# POTENCIA.net
KiCad netlist of a schematic drawn in Altium Designer
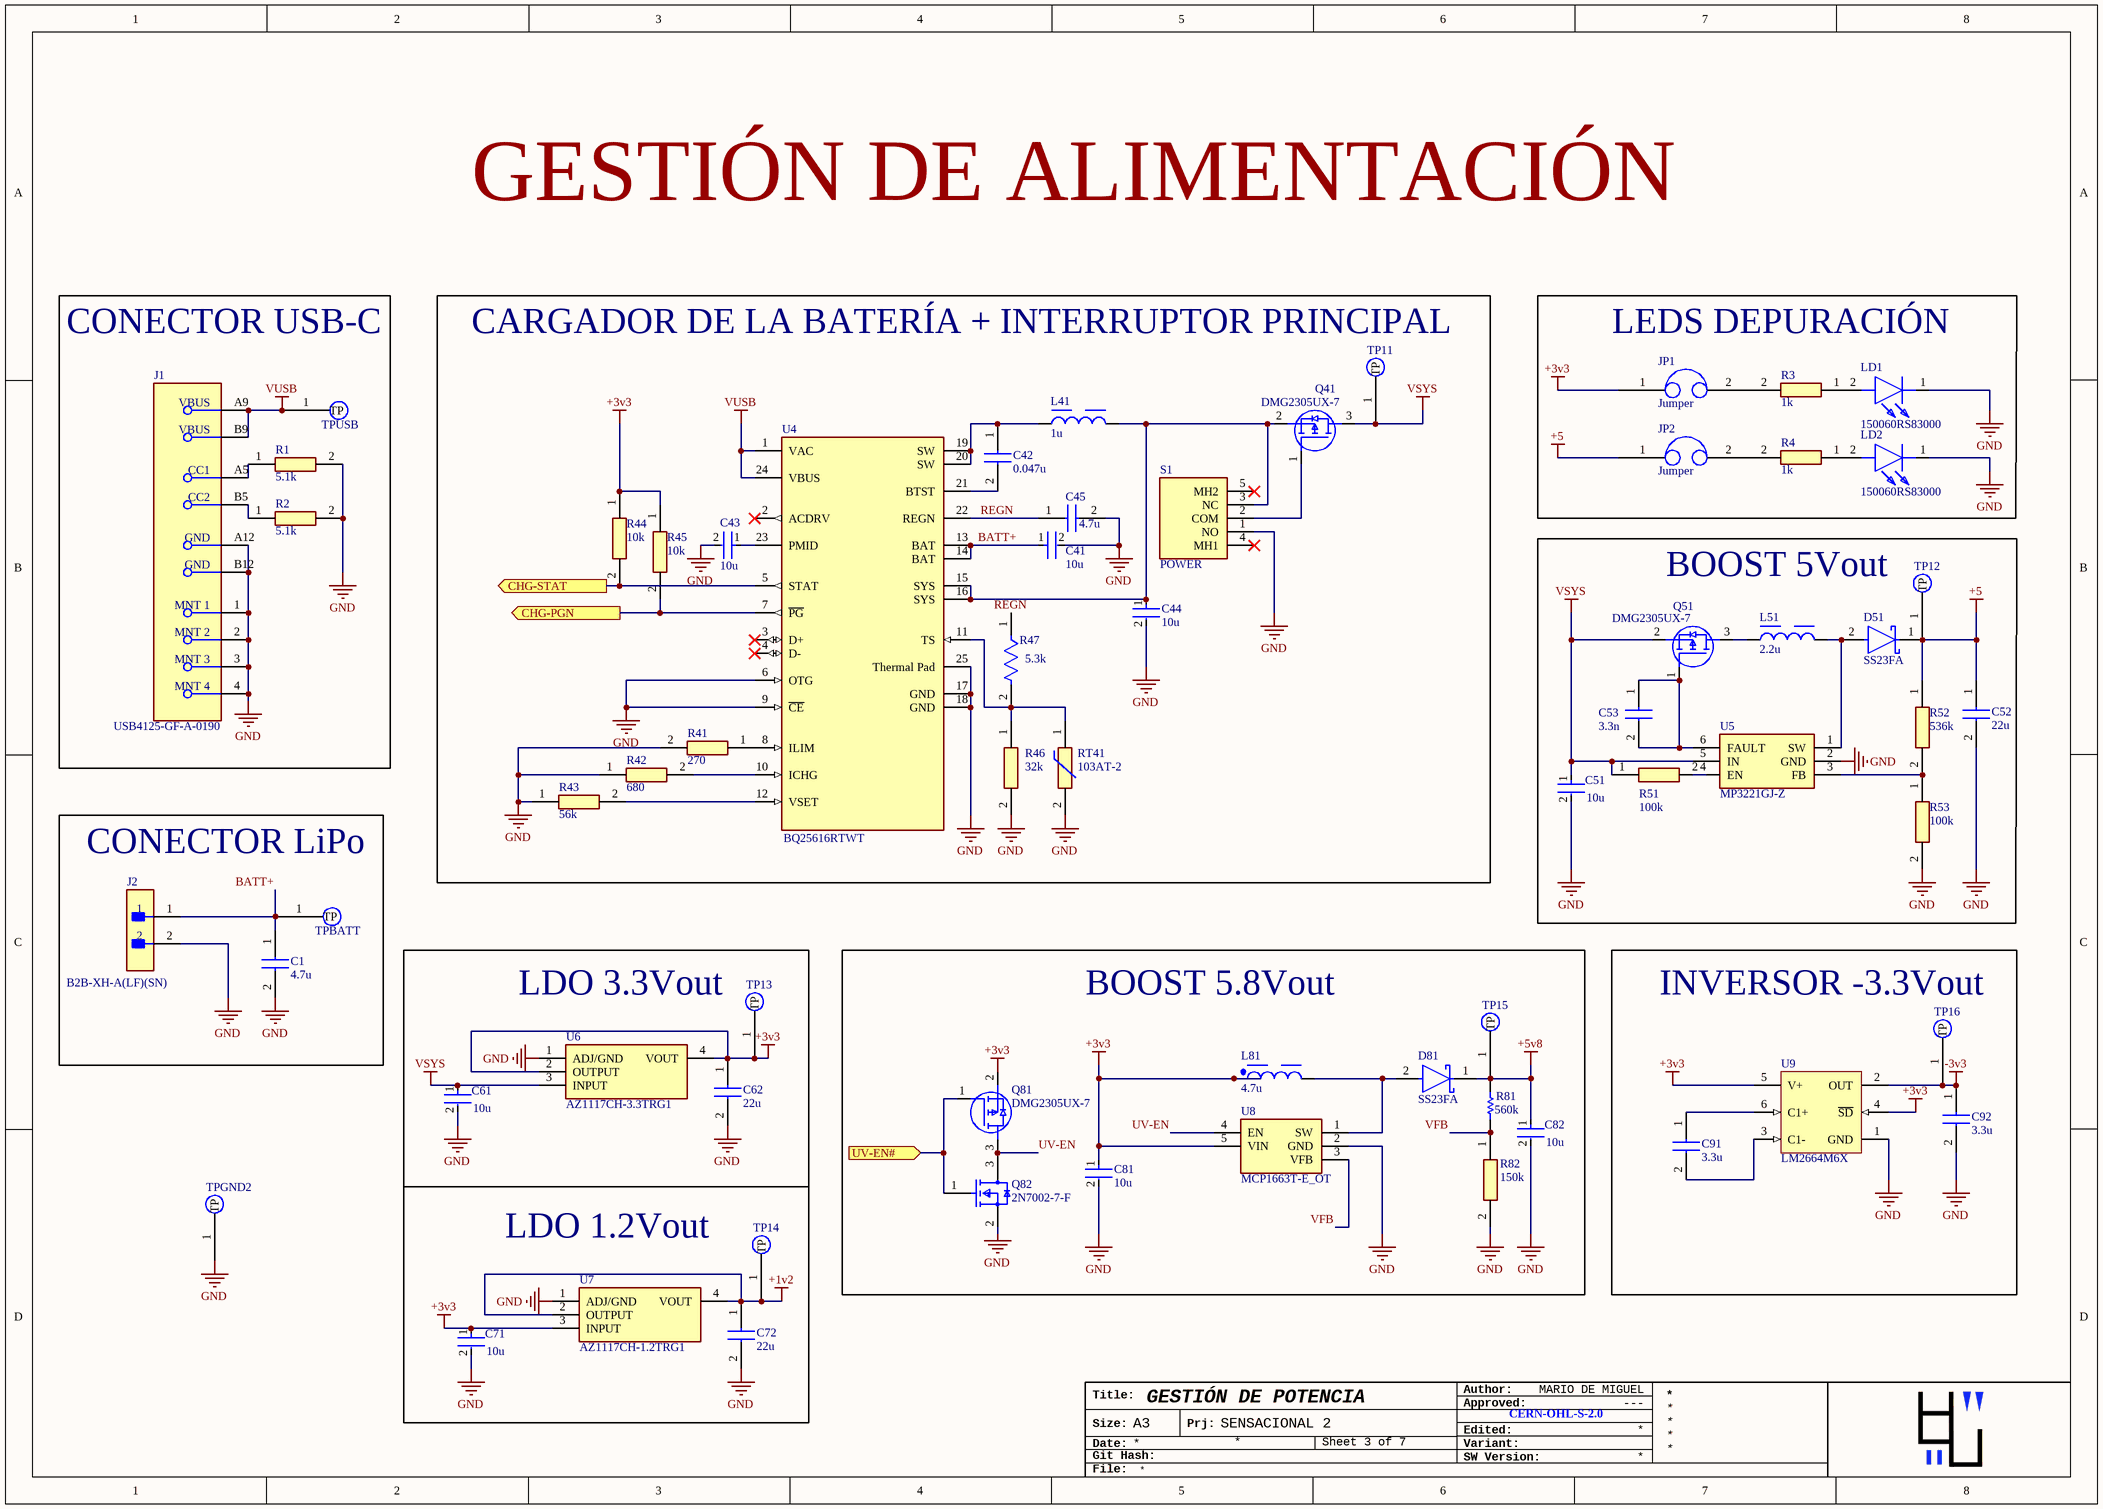
[diagram p0: POTENCIA.SchDoc]

(export (version "E")
  (design (tool "Eeschema 10.0.6"))
  (components
    (comp (ref "C1")
      (value "4.7u")
      (footprint "SamacSys:C0805")
      (description "Capacitor")
      (fields
        (field (name "MANUFACTURER_PART_NUMBER") "C0805X475J8RACAUTO")
        (field (name "MOUSER PART NUMBER") "80-C0805X475J8RAUTO")
      )
      (libsource (lib "*") (part "C0805X475J8RACAUTO"))
    )
    (comp (ref "C41")
      (value "10u")
      (footprint "FP-C2012-125-0_2-MFG")
      (description "Multilayer Ceramic Capacitors 10μF ±10% 10V X7R SMD 0805")
      (fields (field (name "TOLERANCE") "10%") (field (name "VOLTAGE") "10V"))
      (libsource (lib "Altium Content Vault") (part "b4654b650e69147ec39a6b967a45e02"))
    )
    (comp (ref "C42")
      (value "0.047u")
      (footprint "SamacSys:CAPC1608X89N")
      (description "Capacitor")
      (fields
        (field (name "MANUFACTURER_PART_NUMBER") "KAM15AR71H473KM")
        (field (name "MOUSER PART NUMBER") "581-KAM15AR71H473KM")
      )
      (libsource (lib "*") (part "KAM15AR71H473KM"))
    )
    (comp (ref "C43")
      (value "10u")
      (footprint "FP-C2012-125-0_2-MFG")
      (description "Multilayer Ceramic Capacitors 10μF ±10% 10V X7R SMD 0805")
      (fields (field (name "TOLERANCE") "10%") (field (name "VOLTAGE") "10V"))
      (libsource (lib "Altium Content Vault") (part "b4654b650e69147ec39a6b967a45e02"))
    )
    (comp (ref "C44")
      (value "10u")
      (footprint "FP-C2012-125-0_2-MFG")
      (description "Multilayer Ceramic Capacitors 10μF ±10% 10V X7R SMD 0805")
      (fields (field (name "TOLERANCE") "10%") (field (name "VOLTAGE") "10V"))
      (libsource (lib "Altium Content Vault") (part "b4654b650e69147ec39a6b967a45e02"))
    )
    (comp (ref "C45")
      (value "4.7u")
      (footprint "SamacSys:C0805")
      (description "Capacitor")
      (fields
        (field (name "MANUFACTURER_PART_NUMBER") "C0805X475J8RACAUTO")
        (field (name "MOUSER PART NUMBER") "80-C0805X475J8RAUTO")
      )
      (libsource (lib "*") (part "C0805X475J8RACAUTO"))
    )
    (comp (ref "C51")
      (value "10u")
      (footprint "FP-C2012-125-0_2-MFG")
      (description "Multilayer Ceramic Capacitors 10μF ±10% 10V X7R SMD 0805")
      (fields (field (name "TOLERANCE") "10%") (field (name "VOLTAGE") "10V"))
      (libsource (lib "Altium Content Vault") (part "b4654b650e69147ec39a6b967a45e02"))
    )
    (comp (ref "C52")
      (value "22u")
      (footprint "SamacSys:CAPC3216X200N")
      (description "Capacitor")
      (fields (field (name "MANUFACTURER_PART_NUMBER") "GCJ31CC71C226ME02L"))
      (libsource (lib "*") (part "GCJ31CC71C226ME02L"))
    )
    (comp (ref "C53")
      (value "3.3n")
      (footprint "SamacSys:CAPC2012X130N")
      (description "Capacitor")
      (fields (field (name "MANUFACTURER_PART_NUMBER") "GRM21AR7LU332KW01D"))
      (libsource (lib "*") (part "GRM21AR7LU332KW01D"))
    )
    (comp (ref "C61")
      (value "10u")
      (footprint "FP-C2012-125-0_2-MFG")
      (description "Multilayer Ceramic Capacitors 10μF ±10% 10V X7R SMD 0805")
      (fields (field (name "TOLERANCE") "10%") (field (name "VOLTAGE") "10V"))
      (libsource (lib "Altium Content Vault") (part "b4654b650e69147ec39a6b967a45e02"))
    )
    (comp (ref "C62")
      (value "22u")
      (footprint "SamacSys:CAPC3216X200N")
      (description "Capacitor")
      (fields (field (name "MANUFACTURER_PART_NUMBER") "GCJ31CC71C226ME02L"))
      (libsource (lib "*") (part "GCJ31CC71C226ME02L"))
    )
    (comp (ref "C71")
      (value "10u")
      (footprint "FP-C2012-125-0_2-MFG")
      (description "Multilayer Ceramic Capacitors 10μF ±10% 10V X7R SMD 0805")
      (fields (field (name "TOLERANCE") "10%") (field (name "VOLTAGE") "10V"))
      (libsource (lib "Altium Content Vault") (part "b4654b650e69147ec39a6b967a45e02"))
    )
    (comp (ref "C72")
      (value "22u")
      (footprint "SamacSys:CAPC3216X200N")
      (description "Capacitor")
      (fields (field (name "MANUFACTURER_PART_NUMBER") "GCJ31CC71C226ME02L"))
      (libsource (lib "*") (part "GCJ31CC71C226ME02L"))
    )
    (comp (ref "C81")
      (value "10u")
      (footprint "FP-C2012-125-0_2-MFG")
      (description "Multilayer Ceramic Capacitors 10μF ±10% 10V X7R SMD 0805")
      (fields (field (name "TOLERANCE") "10%") (field (name "VOLTAGE") "10V"))
      (libsource (lib "Altium Content Vault") (part "b4654b650e69147ec39a6b967a45e02"))
    )
    (comp (ref "C82")
      (value "10u")
      (footprint "FP-C2012-125-0_2-MFG")
      (description "Multilayer Ceramic Capacitors 10μF ±10% 10V X7R SMD 0805")
      (fields (field (name "TOLERANCE") "10%") (field (name "VOLTAGE") "10V"))
      (libsource (lib "Altium Content Vault") (part "b4654b650e69147ec39a6b967a45e02"))
    )
    (comp (ref "C91")
      (value "3.3u")
      (footprint "SamacSys:CAPC1608X80N")
      (description "Capacitor")
      (fields
        (field (name "MANUFACTURER_PART_NUMBER") "C1608X5R1V335K080AC")
        (field (name "MOUSER PART NUMBER") "810-C1608X5R1V335KAC")
      )
      (libsource (lib "*") (part "C1608X5R1V335K080AC"))
    )
    (comp (ref "C92")
      (value "3.3u")
      (footprint "SamacSys:CAPC1608X80N")
      (description "Capacitor")
      (fields
        (field (name "MANUFACTURER_PART_NUMBER") "C1608X5R1V335K080AC")
        (field (name "MOUSER PART NUMBER") "810-C1608X5R1V335KAC")
      )
      (libsource (lib "*") (part "C1608X5R1V335K080AC"))
    )
    (comp (ref "D51")
      (value "SS23FA")
      (footprint "FP-425AB-MFG")
      (description "SS23FA 2 A, 30 V Surface Mount Schottky Barrier Rectifiers")
      (libsource (lib "Altium Content Vault") (part "1d6ec82d83fb6aee721767c19dac4b9"))
    )
    (comp (ref "D81")
      (value "SS23FA")
      (footprint "FP-425AB-MFG")
      (description "SS23FA 2 A, 30 V Surface Mount Schottky Barrier Rectifiers")
      (libsource (lib "Altium Content Vault") (part "1d6ec82d83fb6aee721767c19dac4b9"))
    )
    (comp (ref "J1")
      (value "USB4125-GF-A-0190")
      (footprint "FP-USB4125-GF-A-0190-MFG")
      (description "CONN RCPT TYPE C 6P SMD RA")
      (libsource (lib "Altium Content Vault") (part "a055484d46e58b234844902c9fd883a"))
    )
    (comp (ref "J2")
      (value "B2B-XH-A(LF)(SN)")
      (footprint "FP-B2B-XH-A_LF_SN-MFG")
      (description "CONN HEADER VERT 2POS 2.5MM")
      (libsource (lib "Altium Content Vault") (part "3bc925449376181038e59eaffc5286c"))
    )
    (comp (ref "JP1") (value "Jumper") (footprint "JUMPER_SHUNT") (libsource (lib "headers") (part "Shunt")))
    (comp (ref "JP2") (value "Jumper") (footprint "JUMPER_SHUNT") (libsource (lib "headers") (part "Shunt")))
    (comp (ref "L41")
      (value "1u")
      (footprint "WE-MAPI_3015")
      (fields (field (name "TOLERANCE") "20%"))
      (libsource (lib "Altium Content Vault") (part "Inductor - 3"))
    )
    (comp (ref "L51")
      (value "2.2u")
      (footprint "WE-LHMI_4012")
      (description "74437321022 General Purpose Inductor, 2.2uH, 20%, 1 Element, Powdered Iron-Core, SMD, 1816")
      (fields (field (name "TOLERANCE") "20%"))
      (libsource (lib "Altium Content Vault") (part "Inductor - 3"))
    )
    (comp (ref "L81")
      (value "4.7u")
      (footprint "WE-PD_7332")
      (fields (field (name "TOLERANCE") "20%"))
      (libsource (lib "Altium Content Vault") (part "Inductor - 2"))
    )
    (comp (ref "LD1")
      (value "150060RS83000")
      (footprint "SamacSys:LEDC1608X95N")
      (description "LED")
      (libsource (lib "*") (part "150060RS83000"))
    )
    (comp (ref "LD2")
      (value "150060RS83000")
      (footprint "SamacSys:LEDC1608X95N")
      (description "LED")
      (libsource (lib "*") (part "150060RS83000"))
    )
    (comp (ref "Q41")
      (value "DMG2305UX-7")
      (footprint "SamacSys:SOT96P240X115-3N")
      (description "MOSFET (P-Channel)")
      (fields (field (name "MOUSER PART NUMBER") "621-DMG2305UX-7"))
      (libsource (lib "*") (part "DMG2305UX-7"))
    )
    (comp (ref "Q51")
      (value "DMG2305UX-7")
      (footprint "SamacSys:SOT96P240X115-3N")
      (description "MOSFET (P-Channel)")
      (fields (field (name "MOUSER PART NUMBER") "621-DMG2305UX-7"))
      (libsource (lib "*") (part "DMG2305UX-7"))
    )
    (comp (ref "Q81")
      (value "DMG2305UX-7")
      (footprint "SamacSys:SOT96P240X115-3N")
      (description "MOSFET (P-Channel)")
      (fields (field (name "MOUSER PART NUMBER") "621-DMG2305UX-7"))
      (libsource (lib "*") (part "DMG2305UX-7"))
    )
    (comp (ref "Q82")
      (value "2N7002-7-F")
      (footprint "FP-SOT23-MFG")
      (description "MOSFET N-CH 60V 115MA SOT23-3")
      (fields (field (name "VOLTAGE") "60V"))
      (libsource (lib "Altium Content Vault") (part "3b9c635fedb024a5347a57b145af9cc"))
    )
    (comp (ref "R1")
      (value "5.1k")
      (footprint "SamacSys:RESC1608X55N")
      (description "Resistor")
      (fields
        (field (name "MANUFACTURER_PART_NUMBER") "RC0603FR-075K1L")
        (field (name "MOUSER PART NUMBER") "603-RC0603FR-075K1L")
      )
      (libsource (lib "*") (part "RC0603FR-075K1L"))
    )
    (comp (ref "R2")
      (value "5.1k")
      (footprint "SamacSys:RESC1608X55N")
      (description "Resistor")
      (fields
        (field (name "MANUFACTURER_PART_NUMBER") "RC0603FR-075K1L")
        (field (name "MOUSER PART NUMBER") "603-RC0603FR-075K1L")
      )
      (libsource (lib "*") (part "RC0603FR-075K1L"))
    )
    (comp (ref "R3")
      (value "1k")
      (footprint "SamacSys:ERA6AEB101V")
      (description "Resistor")
      (fields
        (field (name "MANUFACTURER_PART_NUMBER") "ERA-6ARW102V")
        (field (name "MOUSER PART NUMBER") "667-ERA-6ARW102V")
      )
      (libsource (lib "*") (part "ERA-6ARW102V"))
    )
    (comp (ref "R4")
      (value "1k")
      (footprint "SamacSys:ERA6AEB101V")
      (description "Resistor")
      (fields
        (field (name "MANUFACTURER_PART_NUMBER") "ERA-6ARW102V")
        (field (name "MOUSER PART NUMBER") "667-ERA-6ARW102V")
      )
      (libsource (lib "*") (part "ERA-6ARW102V"))
    )
    (comp (ref "R41")
      (value "270")
      (footprint "SamacSys:ERA3AEB101V")
      (description "Resistor")
      (fields
        (field (name "MANUFACTURER_PART_NUMBER") "ERA-3AEB271V")
        (field (name "MOUSER PART NUMBER") "667-ERA-3AEB271V")
      )
      (libsource (lib "*") (part "ERA-3AEB271V"))
    )
    (comp (ref "R42")
      (value "680")
      (footprint "SamacSys:RESC1608X55N")
      (description "Resistor")
      (fields
        (field (name "MANUFACTURER_PART_NUMBER") "CR0603-FX-6800ELF")
        (field (name "MOUSER PART NUMBER") "652-CR0603FX-6800ELF")
      )
      (libsource (lib "*") (part "CR0603-FX-6800ELF"))
    )
    (comp (ref "R43")
      (value "56k")
      (footprint "SamacSys:ERA3AEB101V")
      (description "Resistor")
      (fields
        (field (name "MANUFACTURER_PART_NUMBER") "ERA-3ARB563V")
        (field (name "MOUSER PART NUMBER") "667-ERA-3ARB563V")
      )
      (libsource (lib "*") (part "ERA-3ARB563V"))
    )
    (comp (ref "R44")
      (value "10k")
      (footprint "SamacSys:RESC1005X40N")
      (description "Resistor")
      (fields
        (field (name "MANUFACTURER_PART_NUMBER") "RCA040210K0JNED")
        (field (name "MOUSER PART NUMBER") "71-RCA040210K0JNED")
      )
      (libsource (lib "*") (part "RCA040210K0JNED"))
    )
    (comp (ref "R45")
      (value "10k")
      (footprint "SamacSys:RESC1005X40N")
      (description "Resistor")
      (fields
        (field (name "MANUFACTURER_PART_NUMBER") "RCA040210K0JNED")
        (field (name "MOUSER PART NUMBER") "71-RCA040210K0JNED")
      )
      (libsource (lib "*") (part "RCA040210K0JNED"))
    )
    (comp (ref "R46")
      (value "32k")
      (footprint "SamacSys:RESC1608X55N")
      (description "Resistor")
      (fields
        (field (name "MANUFACTURER_PART_NUMBER") "RT0603BRD0732KL")
        (field (name "MOUSER PART NUMBER") "603-RT0603BRD0732KL")
      )
      (libsource (lib "*") (part "RT0603BRD0732KL"))
    )
    (comp (ref "R47")
      (value "5.3k")
      (footprint "FP-TNPW0603-e3-MFG")
      (description "RES 5.3K OHM 0.1% 1/10W 0603")
      (fields (field (name "TOLERANCE") "0.1%"))
      (libsource (lib "Altium Content Vault") (part "1029c3af85768c4190bb7ad29bc67b5"))
    )
    (comp (ref "R51")
      (value "100k")
      (footprint "SamacSys:ERA3AEB101V")
      (description "Resistor")
      (fields
        (field (name "MANUFACTURER_PART_NUMBER") "ERA-3AED104V")
        (field (name "MOUSER PART NUMBER") "667-ERA-3AED104V")
      )
      (libsource (lib "*") (part "ERA-3AED104V"))
    )
    (comp (ref "R52")
      (value "536k")
      (footprint "SamacSys:RESC1608X55N")
      (description "Resistor")
      (fields
        (field (name "MANUFACTURER_PART_NUMBER") "ERJ-3EKF5363V")
        (field (name "MOUSER PART NUMBER") "667-ERJ-3EKF5363V")
      )
      (libsource (lib "*") (part "ERJ-3EKF5363V"))
    )
    (comp (ref "R53")
      (value "100k")
      (footprint "SamacSys:ERA3AEB101V")
      (description "Resistor")
      (fields
        (field (name "MANUFACTURER_PART_NUMBER") "ERA-3AED104V")
        (field (name "MOUSER PART NUMBER") "667-ERA-3AED104V")
      )
      (libsource (lib "") (part "ERA-3AED104V_1"))
    )
    (comp (ref "R81")
      (value "560k")
      (footprint "RESC1608X55X30ML15T15")
      (fields (field (name "MANUFACTURER") "Panasonic") (field (name "PART NUMBER") "ERJ-3GEYJ564V"))
      (libsource (lib "Altium Content Vault") (part "RES"))
    )
    (comp (ref "R82")
      (value "150k")
      (footprint "SamacSys:RESC1608X55N")
      (description "Resistor")
      (fields
        (field (name "MANUFACTURER_PART_NUMBER") "ERJ-S03J154V")
        (field (name "MOUSER PART NUMBER") "667-ERJ-S03J154V")
      )
      (libsource (lib "*") (part "ERJ-S03J154V"))
    )
    (comp (ref "RT41")
      (value "103AT-2")
      (footprint "SamacSys:103AT2")
      (description "Thermistor")
      (fields (field (name "MOUSER PART NUMBER") "954-103AT-2"))
      (libsource (lib "*") (part "103AT-2"))
    )
    (comp (ref "S1")
      (value "POWER")
      (footprint "SamacSys:OS102011MS2QS1")
      (description "Switch")
      (fields
        (field (name "MANUFACTURER_PART_NUMBER") "OS102011MS2QS1")
        (field (name "MOUSER PART NUMBER") "611-OS102011MS2QS1")
      )
      (libsource (lib "*") (part "OS102011MS2QS1"))
    )
    (comp (ref "TP11")
      (value "Testpoint")
      (footprint "Testpoint_TH")
      (libsource (lib "headers") (part "Testpoint"))
    )
    (comp (ref "TP12")
      (value "Testpoint")
      (footprint "Testpoint_TH")
      (libsource (lib "headers") (part "Testpoint"))
    )
    (comp (ref "TP13")
      (value "Testpoint")
      (footprint "Testpoint_TH")
      (libsource (lib "headers") (part "Testpoint"))
    )
    (comp (ref "TP14")
      (value "Testpoint")
      (footprint "Testpoint_TH")
      (libsource (lib "headers") (part "Testpoint"))
    )
    (comp (ref "TP15")
      (value "Testpoint")
      (footprint "Testpoint_TH")
      (libsource (lib "headers") (part "Testpoint"))
    )
    (comp (ref "TP16")
      (value "Testpoint")
      (footprint "Testpoint_TH")
      (libsource (lib "headers") (part "Testpoint"))
    )
    (comp (ref "TPBATT")
      (value "Testpoint")
      (footprint "Testpoint_TH")
      (libsource (lib "headers") (part "Testpoint"))
    )
    (comp (ref "TPGND2")
      (value "Testpoint")
      (footprint "Testpoint_TH")
      (libsource (lib "headers") (part "Testpoint"))
    )
    (comp (ref "TPUSB")
      (value "Testpoint")
      (footprint "Testpoint_TH")
      (libsource (lib "headers") (part "Testpoint"))
    )
    (comp (ref "U4")
      (value "BQ25616RTWT")
      (footprint "FP-RTW0024H-IPC_B")
      (description "BQ25616RTWR/T")
      (libsource (lib "Altium Content Vault") (part "cab04b428aadb88d2d607b4ef955cae"))
    )
    (comp (ref "U5")
      (value "MP3221GJ-Z")
      (footprint "SamacSys:SOT95P280X100-6N")
      (description "Integrated Circuit")
      (fields (field (name "MOUSER PART NUMBER") "946-MP3221GJ-Z"))
      (libsource (lib "*") (part "MP3221GJ-Z"))
    )
    (comp (ref "U6")
      (value "AZ1117CH-3.3TRG1")
      (footprint "SamacSys:SOT230P700X180-4N")
      (description "Integrated Circuit")
      (fields (field (name "MOUSER PART NUMBER") "621-AZ1117CH-3.3TRG1"))
      (libsource (lib "SamacSys") (part "AZ1117CH-3.3TRG1"))
    )
    (comp (ref "U7")
      (value "AZ1117CH-1.2TRG1")
      (footprint "SamacSys:SOT230P700X180-4N")
      (description "Integrated Circuit")
      (fields (field (name "MOUSER PART NUMBER") "621-AZ1117CH-1.2TRG1"))
      (libsource (lib "SamacSys") (part "AZ1117CH-1.2TRG1"))
    )
    (comp (ref "U8")
      (value "MCP1663T-E_OT")
      (footprint "SamacSys:SOT95P270X145-5N")
      (description "Integrated Circuit")
      (fields
        (field (name "MANUFACTURER_PART_NUMBER") "MCP1663T-E/OT")
        (field (name "MOUSER PART NUMBER") "579-MCP1663T-E/OT")
      )
      (libsource (lib "*") (part "MCP1663T-E_OT"))
    )
    (comp (ref "U9")
      (value "LM2664M6X")
      (footprint "DBV0006A_N")
      (description "Switched Capacitor Voltage Converter, 6-pin SOT-23")
      (fields (field (name "MANUFACTURER") "Texas Instruments"))
      (libsource (lib "Altium Content Vault") (part "PM-CHP-LM2664M6-6"))
    )
  )
  (nets
    (net (code "1") (name "+1v2") (class "Default")
      (node (ref "C72") (pin "1") (pinfunction "1_1") (pintype "passive"))
      (node (ref "TP14") (pin "1") (pinfunction "TP_1") (pintype "passive"))
      (node (ref "U7") (pin "2") (pinfunction "OUTPUT_2") (pintype "passive"))
      (node (ref "U7") (pin "4") (pinfunction "VOUT_4") (pintype "passive"))
    )
    (net (code "2") (name "+3v3") (class "Default")
      (node (ref "C62") (pin "1") (pinfunction "1_1") (pintype "passive"))
      (node (ref "C71") (pin "1") (pinfunction "1_1") (pintype "passive"))
      (node (ref "C81") (pin "1") (pinfunction "1_1") (pintype "passive"))
      (node (ref "JP1") (pin "1") (pinfunction "16_1") (pintype "passive"))
      (node (ref "L81") (pin "1") (pinfunction "1_1") (pintype "passive"))
      (node (ref "Q81") (pin "2") (pinfunction "S_2") (pintype "passive"))
      (node (ref "R44") (pin "1") (pinfunction "1_1") (pintype "passive"))
      (node (ref "R45") (pin "1") (pinfunction "1_1") (pintype "passive"))
      (node (ref "TP13") (pin "1") (pinfunction "TP_1") (pintype "passive"))
      (node (ref "U6") (pin "2") (pinfunction "OUTPUT_2") (pintype "passive"))
      (node (ref "U6") (pin "4") (pinfunction "VOUT_4") (pintype "passive"))
      (node (ref "U7") (pin "3") (pinfunction "INPUT_3") (pintype "passive"))
      (node (ref "U8") (pin "5") (pinfunction "VIN_5") (pintype "passive"))
      (node (ref "U9") (pin "4") (pinfunction "~{SD}_4") (pintype "input"))
      (node (ref "U9") (pin "5") (pinfunction "V+_5") (pintype "power_in"))
    )
    (net (code "3") (name "+5") (class "Default")
      (node (ref "C52") (pin "1") (pinfunction "1_1") (pintype "passive"))
      (node (ref "D51") (pin "1") (pinfunction "C_1") (pintype "passive"))
      (node (ref "JP2") (pin "1") (pinfunction "16_1") (pintype "passive"))
      (node (ref "R52") (pin "1") (pinfunction "1_1") (pintype "passive"))
      (node (ref "TP12") (pin "1") (pinfunction "TP_1") (pintype "passive"))
    )
    (net (code "4") (name "+5v8") (class "Default")
      (node (ref "C82") (pin "1") (pinfunction "1_1") (pintype "passive"))
      (node (ref "D81") (pin "1") (pinfunction "C_1") (pintype "passive"))
      (node (ref "R81") (pin "2") (pinfunction "2_2") (pintype "passive"))
      (node (ref "TP15") (pin "1") (pinfunction "TP_1") (pintype "passive"))
    )
    (net (code "5") (name "-3v3") (class "Default")
      (node (ref "C92") (pin "1") (pinfunction "1_1") (pintype "passive"))
      (node (ref "TP16") (pin "1") (pinfunction "TP_1") (pintype "passive"))
      (node (ref "U9") (pin "2") (pinfunction "OUT_2") (pintype "power_in"))
    )
    (net (code "6") (name "/BATT+") (class "Default")
      (node (ref "C1") (pin "1") (pinfunction "1_1") (pintype "passive"))
      (node (ref "C41") (pin "1") (pinfunction "1_1") (pintype "passive"))
      (node (ref "J2") (pin "1") (pinfunction "1_1") (pintype "passive"))
      (node (ref "TPBATT") (pin "1") (pinfunction "TP_1") (pintype "passive"))
      (node (ref "U4") (pin "13") (pinfunction "BAT_13") (pintype "power_in"))
      (node (ref "U4") (pin "14") (pinfunction "BAT_14") (pintype "power_in"))
    )
    (net (code "7") (name "/CHG-PGN") (class "Default")
      (node (ref "R45") (pin "2") (pinfunction "2_2") (pintype "passive"))
      (node (ref "U4") (pin "7") (pinfunction "~{PG}_7") (pintype "output"))
    )
    (net (code "8") (name "/CHG-STAT") (class "Default")
      (node (ref "R44") (pin "2") (pinfunction "2_2") (pintype "passive"))
      (node (ref "U4") (pin "5") (pinfunction "STAT_5") (pintype "output"))
    )
    (net (code "9") (name "/REGN") (class "Default")
      (node (ref "C45") (pin "1") (pinfunction "1_1") (pintype "passive"))
      (node (ref "R47") (pin "1") (pinfunction "1_1") (pintype "passive"))
      (node (ref "U4") (pin "22") (pinfunction "REGN_22") (pintype "power_in"))
    )
    (net (code "10") (name "/UV-EN") (class "Default")
      (node (ref "Q81") (pin "3") (pinfunction "D_3") (pintype "passive"))
      (node (ref "Q82") (pin "3") (pinfunction "D_3") (pintype "passive"))
      (node (ref "U8") (pin "4") (pinfunction "EN_4") (pintype "passive"))
    )
    (net (code "11") (name "/UV-EN#") (class "Default")
      (node (ref "Q81") (pin "1") (pinfunction "G_1") (pintype "passive"))
      (node (ref "Q82") (pin "1") (pinfunction "G_1") (pintype "passive"))
    )
    (net (code "12") (name "/VFB") (class "Default")
      (node (ref "R81") (pin "1") (pinfunction "1_1") (pintype "passive"))
      (node (ref "R82") (pin "1") (pinfunction "1_1") (pintype "passive"))
      (node (ref "U8") (pin "3") (pinfunction "VFB_3") (pintype "passive"))
    )
    (net (code "13") (name "GND") (class "Default")
      (node (ref "C1") (pin "2") (pinfunction "2_2") (pintype "passive"))
      (node (ref "C41") (pin "2") (pinfunction "2_2") (pintype "passive"))
      (node (ref "C43") (pin "2") (pinfunction "2_2") (pintype "passive"))
      (node (ref "C44") (pin "2") (pinfunction "2_2") (pintype "passive"))
      (node (ref "C45") (pin "2") (pinfunction "2_2") (pintype "passive"))
      (node (ref "C51") (pin "2") (pinfunction "2_2") (pintype "passive"))
      (node (ref "C52") (pin "2") (pinfunction "2_2") (pintype "passive"))
      (node (ref "C61") (pin "2") (pinfunction "2_2") (pintype "passive"))
      (node (ref "C62") (pin "2") (pinfunction "2_2") (pintype "passive"))
      (node (ref "C71") (pin "2") (pinfunction "2_2") (pintype "passive"))
      (node (ref "C72") (pin "2") (pinfunction "2_2") (pintype "passive"))
      (node (ref "C81") (pin "2") (pinfunction "2_2") (pintype "passive"))
      (node (ref "C82") (pin "2") (pinfunction "2_2") (pintype "passive"))
      (node (ref "C92") (pin "2") (pinfunction "2_2") (pintype "passive"))
      (node (ref "J1") (pin "1") (pinfunction "MNT_1_1") (pintype "passive"))
      (node (ref "J1") (pin "2") (pinfunction "MNT_2_2") (pintype "passive"))
      (node (ref "J1") (pin "3") (pinfunction "MNT_3_3") (pintype "passive"))
      (node (ref "J1") (pin "4") (pinfunction "MNT_4_4") (pintype "passive"))
      (node (ref "J1") (pin "A12") (pinfunction "GND_A12") (pintype "passive"))
      (node (ref "J1") (pin "B12") (pinfunction "GND_B12") (pintype "passive"))
      (node (ref "J2") (pin "2") (pinfunction "2_2") (pintype "passive"))
      (node (ref "LD1") (pin "1") (pinfunction "K_1") (pintype "passive"))
      (node (ref "LD2") (pin "1") (pinfunction "K_1") (pintype "passive"))
      (node (ref "Q82") (pin "2") (pinfunction "S_2") (pintype "passive"))
      (node (ref "R1") (pin "2") (pinfunction "2_2") (pintype "passive"))
      (node (ref "R2") (pin "2") (pinfunction "2_2") (pintype "passive"))
      (node (ref "R41") (pin "2") (pinfunction "2_2") (pintype "passive"))
      (node (ref "R42") (pin "1") (pinfunction "1_1") (pintype "passive"))
      (node (ref "R43") (pin "1") (pinfunction "1_1") (pintype "passive"))
      (node (ref "R46") (pin "2") (pinfunction "2_2") (pintype "passive"))
      (node (ref "R53") (pin "2") (pinfunction "2_2") (pintype "passive"))
      (node (ref "R82") (pin "2") (pinfunction "2_2") (pintype "passive"))
      (node (ref "RT41") (pin "2") (pinfunction "2_2") (pintype "passive"))
      (node (ref "S1") (pin "1") (pinfunction "NO_1") (pintype "passive"))
      (node (ref "TPGND2") (pin "1") (pinfunction "TP_1") (pintype "passive"))
      (node (ref "U4") (pin "17") (pinfunction "GND_17") (pintype "power_in"))
      (node (ref "U4") (pin "18") (pinfunction "GND_18") (pintype "power_in"))
      (node (ref "U4") (pin "25") (pinfunction "Thermal_Pad_25") (pintype "power_in"))
      (node (ref "U4") (pin "6") (pinfunction "OTG_6") (pintype "input"))
      (node (ref "U4") (pin "9") (pinfunction "~{CE}_9") (pintype "input"))
      (node (ref "U5") (pin "2") (pinfunction "GND_2") (pintype "passive"))
      (node (ref "U6") (pin "1") (pinfunction "ADJ/GND_1") (pintype "passive"))
      (node (ref "U7") (pin "1") (pinfunction "ADJ/GND_1") (pintype "passive"))
      (node (ref "U8") (pin "2") (pinfunction "GND_2") (pintype "passive"))
      (node (ref "U9") (pin "1") (pinfunction "GND_1") (pintype "power_in"))
    )
    (net (code "14") (name "Net-(C42-Pad1)") (class "Default")
      (node (ref "C42") (pin "1") (pinfunction "1_1") (pintype "passive"))
      (node (ref "L41") (pin "1") (pinfunction "1_1") (pintype "passive"))
      (node (ref "U4") (pin "19") (pinfunction "SW_19") (pintype "power_in"))
      (node (ref "U4") (pin "20") (pinfunction "SW_20") (pintype "power_in"))
    )
    (net (code "15") (name "Net-(D51-A)") (class "Default")
      (node (ref "D51") (pin "2") (pinfunction "A_2") (pintype "passive"))
      (node (ref "L51") (pin "2") (pinfunction "2_2") (pintype "passive"))
      (node (ref "U5") (pin "1") (pinfunction "SW_1") (pintype "passive"))
    )
    (net (code "16") (name "Net-(D81-A)") (class "Default")
      (node (ref "D81") (pin "2") (pinfunction "A_2") (pintype "passive"))
      (node (ref "L81") (pin "2") (pinfunction "2_2") (pintype "passive"))
      (node (ref "U8") (pin "1") (pinfunction "SW_1") (pintype "passive"))
    )
    (net (code "17") (name "Net-(J1-CC1)") (class "Default")
      (node (ref "J1") (pin "A5") (pinfunction "CC1_A5") (pintype "passive"))
      (node (ref "R1") (pin "1") (pinfunction "1_1") (pintype "passive"))
    )
    (net (code "18") (name "Net-(J1-CC2)") (class "Default")
      (node (ref "J1") (pin "B5") (pinfunction "CC2_B5") (pintype "passive"))
      (node (ref "R2") (pin "1") (pinfunction "1_1") (pintype "passive"))
    )
    (net (code "19") (name "Net-(JP1-Pad2)") (class "Default")
      (node (ref "JP1") (pin "2") (pintype "passive"))
      (node (ref "R3") (pin "2") (pinfunction "2_2") (pintype "passive"))
    )
    (net (code "20") (name "Net-(JP2-Pad2)") (class "Default")
      (node (ref "JP2") (pin "2") (pintype "passive"))
      (node (ref "R4") (pin "2") (pinfunction "2_2") (pintype "passive"))
    )
    (net (code "21") (name "Net-(LD1-A)") (class "Default")
      (node (ref "LD1") (pin "2") (pinfunction "A_2") (pintype "passive"))
      (node (ref "R3") (pin "1") (pinfunction "1_1") (pintype "passive"))
    )
    (net (code "22") (name "Net-(LD2-A)") (class "Default")
      (node (ref "LD2") (pin "2") (pinfunction "A_2") (pintype "passive"))
      (node (ref "R4") (pin "1") (pinfunction "1_1") (pintype "passive"))
    )
    (net (code "23") (name "Net-(Q41-G)") (class "Default")
      (node (ref "Q41") (pin "1") (pinfunction "G_1") (pintype "passive"))
      (node (ref "S1") (pin "2") (pinfunction "COM_2") (pintype "passive"))
    )
    (net (code "24") (name "Net-(Q41-S)") (class "Default")
      (node (ref "C44") (pin "1") (pinfunction "1_1") (pintype "passive"))
      (node (ref "L41") (pin "2") (pinfunction "2_2") (pintype "passive"))
      (node (ref "Q41") (pin "2") (pinfunction "S_2") (pintype "passive"))
      (node (ref "S1") (pin "3") (pinfunction "NC_3") (pintype "passive"))
      (node (ref "U4") (pin "15") (pinfunction "SYS_15") (pintype "power_in"))
      (node (ref "U4") (pin "16") (pinfunction "SYS_16") (pintype "power_in"))
    )
    (net (code "25") (name "Net-(Q51-D)") (class "Default")
      (node (ref "L51") (pin "1") (pinfunction "1_1") (pintype "passive"))
      (node (ref "Q51") (pin "3") (pinfunction "D_3") (pintype "passive"))
    )
    (net (code "26") (name "Net-(Q51-G)") (class "Default")
      (node (ref "C53") (pin "1") (pinfunction "1_1") (pintype "passive"))
      (node (ref "C53") (pin "2") (pinfunction "2_2") (pintype "passive"))
      (node (ref "Q51") (pin "1") (pinfunction "G_1") (pintype "passive"))
      (node (ref "U5") (pin "6") (pinfunction "FAULT_6") (pintype "passive"))
    )
    (net (code "27") (name "Net-(U4-BTST)") (class "Default")
      (node (ref "C42") (pin "2") (pinfunction "2_2") (pintype "passive"))
      (node (ref "U4") (pin "21") (pinfunction "BTST_21") (pintype "power_in"))
    )
    (net (code "28") (name "Net-(U4-ICHG)") (class "Default")
      (node (ref "R42") (pin "2") (pinfunction "2_2") (pintype "passive"))
      (node (ref "U4") (pin "10") (pinfunction "ICHG_10") (pintype "input"))
    )
    (net (code "29") (name "Net-(U4-ILIM)") (class "Default")
      (node (ref "R41") (pin "1") (pinfunction "1_1") (pintype "passive"))
      (node (ref "U4") (pin "8") (pinfunction "ILIM_8") (pintype "input"))
    )
    (net (code "30") (name "Net-(U4-PMID)") (class "Default")
      (node (ref "C43") (pin "1") (pinfunction "1_1") (pintype "passive"))
      (node (ref "U4") (pin "23") (pinfunction "PMID_23") (pintype "power_in"))
    )
    (net (code "31") (name "Net-(U4-TS)") (class "Default")
      (node (ref "R46") (pin "1") (pinfunction "1_1") (pintype "passive"))
      (node (ref "R47") (pin "2") (pinfunction "2_2") (pintype "passive"))
      (node (ref "RT41") (pin "1") (pinfunction "1_1") (pintype "passive"))
      (node (ref "U4") (pin "11") (pinfunction "TS_11") (pintype "input"))
    )
    (net (code "32") (name "Net-(U4-VSET)") (class "Default")
      (node (ref "R43") (pin "2") (pinfunction "2_2") (pintype "passive"))
      (node (ref "U4") (pin "12") (pinfunction "VSET_12") (pintype "input"))
    )
    (net (code "33") (name "Net-(U5-EN)") (class "Default")
      (node (ref "R51") (pin "2") (pinfunction "2_2") (pintype "passive"))
      (node (ref "U5") (pin "4") (pinfunction "EN_4") (pintype "passive"))
    )
    (net (code "34") (name "Net-(U5-FB)") (class "Default")
      (node (ref "R52") (pin "2") (pinfunction "2_2") (pintype "passive"))
      (node (ref "R53") (pin "1") (pinfunction "1_1") (pintype "passive"))
      (node (ref "U5") (pin "3") (pinfunction "FB_3") (pintype "passive"))
    )
    (net (code "35") (name "Net-(U9-C1+)") (class "Default")
      (node (ref "C91") (pin "1") (pinfunction "1_1") (pintype "passive"))
      (node (ref "U9") (pin "6") (pinfunction "C1+_6") (pintype "input"))
    )
    (net (code "36") (name "Net-(U9-C1-)") (class "Default")
      (node (ref "C91") (pin "2") (pinfunction "2_2") (pintype "passive"))
      (node (ref "U9") (pin "3") (pinfunction "C1-_3") (pintype "input"))
    )
    (net (code "37") (name "VSYS") (class "Default")
      (node (ref "C51") (pin "1") (pinfunction "1_1") (pintype "passive"))
      (node (ref "C61") (pin "1") (pinfunction "1_1") (pintype "passive"))
      (node (ref "Q41") (pin "3") (pinfunction "D_3") (pintype "passive"))
      (node (ref "Q51") (pin "2") (pinfunction "S_2") (pintype "passive"))
      (node (ref "R51") (pin "1") (pinfunction "1_1") (pintype "passive"))
      (node (ref "TP11") (pin "1") (pinfunction "TP_1") (pintype "passive"))
      (node (ref "U5") (pin "5") (pinfunction "IN_5") (pintype "passive"))
      (node (ref "U6") (pin "3") (pinfunction "INPUT_3") (pintype "passive"))
    )
    (net (code "38") (name "VUSB") (class "Default")
      (node (ref "J1") (pin "A9") (pinfunction "VBUS_A9") (pintype "passive"))
      (node (ref "J1") (pin "B9") (pinfunction "VBUS_B9") (pintype "passive"))
      (node (ref "TPUSB") (pin "1") (pinfunction "TP_1") (pintype "passive"))
      (node (ref "U4") (pin "1") (pinfunction "VAC_1") (pintype "power_in"))
      (node (ref "U4") (pin "24") (pinfunction "VBUS_24") (pintype "power_in"))
    )
    (net (code "39") (name "unconnected-(S1-MH1-Pad4)") (class "Default")
      (node (ref "S1") (pin "4") (pinfunction "MH1_4") (pintype "passive+no_connect"))
    )
    (net (code "40") (name "unconnected-(S1-MH2-Pad5)") (class "Default")
      (node (ref "S1") (pin "5") (pinfunction "MH2_5") (pintype "passive+no_connect"))
    )
    (net (code "41") (name "unconnected-(U4-ACDRV-Pad2)") (class "Default")
      (node (ref "U4") (pin "2") (pinfunction "ACDRV_2") (pintype "output+no_connect"))
    )
    (net (code "42") (name "unconnected-(U4-D+-Pad3)") (class "Default")
      (node (ref "U4") (pin "3") (pinfunction "D+_3") (pintype "bidirectional+no_connect"))
    )
    (net (code "43") (name "unconnected-(U4-D--Pad4)") (class "Default")
      (node (ref "U4") (pin "4") (pinfunction "D-_4") (pintype "bidirectional+no_connect"))
    )
  )
)
